# fpga33-serdes-power.net
KiCad netlist of a schematic drawn in Altium Designer
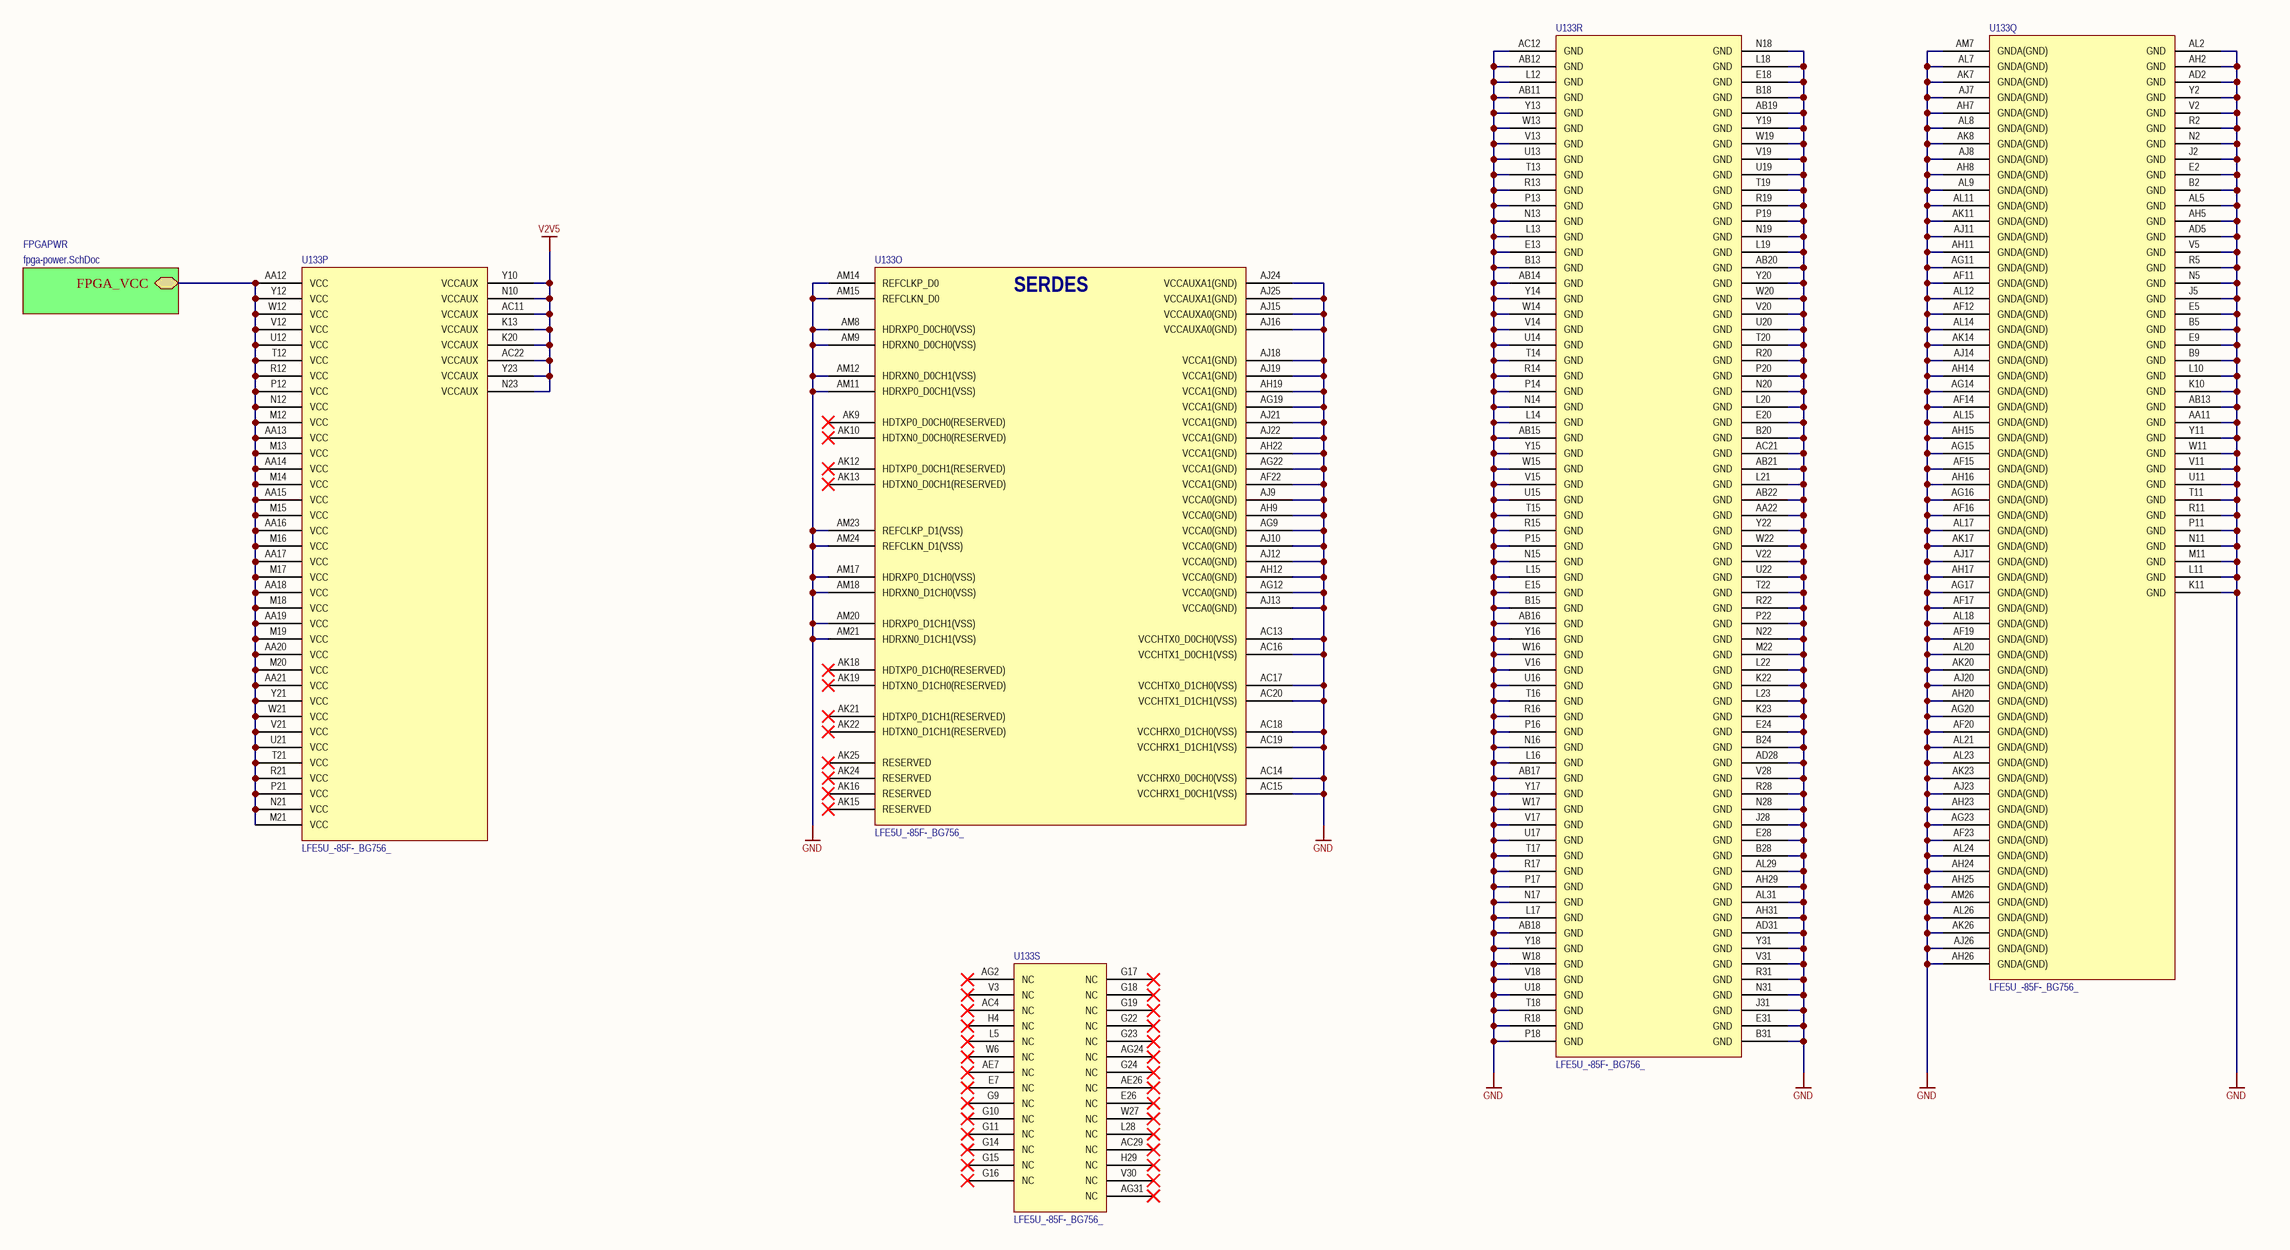
[diagram p0: fpga33-serdes-power.SchDoc]

(export (version "E")
  (design (tool "Eeschema 10.0.6"))
  (components
    (comp (ref "U133")
      (value "LFE5U_-85F-_BG756_")
      (footprint "lattice:caBGA756")
      (description "ECP5 FPGA, 85k LUT, 756-caBGA")
      (fields (field (name "MANUFACTURER") "Lattice Semiconductor"))
      (libsource (lib "lattice") (part "LFE5U_-85F-_BG756_"))
    )
  )
  (nets
    (net (code "1") (name "/FPGA_VCC") (class "Default")
      (node (ref "U133") (pin "AA12") (pinfunction "VCC_AA12") (pintype "power_in"))
      (node (ref "U133") (pin "AA13") (pinfunction "VCC_AA13") (pintype "power_in"))
      (node (ref "U133") (pin "AA14") (pinfunction "VCC_AA14") (pintype "power_in"))
      (node (ref "U133") (pin "AA15") (pinfunction "VCC_AA15") (pintype "power_in"))
      (node (ref "U133") (pin "AA16") (pinfunction "VCC_AA16") (pintype "power_in"))
      (node (ref "U133") (pin "AA17") (pinfunction "VCC_AA17") (pintype "power_in"))
      (node (ref "U133") (pin "AA18") (pinfunction "VCC_AA18") (pintype "power_in"))
      (node (ref "U133") (pin "AA19") (pinfunction "VCC_AA19") (pintype "power_in"))
      (node (ref "U133") (pin "AA20") (pinfunction "VCC_AA20") (pintype "power_in"))
      (node (ref "U133") (pin "AA21") (pinfunction "VCC_AA21") (pintype "power_in"))
      (node (ref "U133") (pin "M12") (pinfunction "VCC_M12") (pintype "power_in"))
      (node (ref "U133") (pin "M13") (pinfunction "VCC_M13") (pintype "power_in"))
      (node (ref "U133") (pin "M14") (pinfunction "VCC_M14") (pintype "power_in"))
      (node (ref "U133") (pin "M15") (pinfunction "VCC_M15") (pintype "power_in"))
      (node (ref "U133") (pin "M16") (pinfunction "VCC_M16") (pintype "power_in"))
      (node (ref "U133") (pin "M17") (pinfunction "VCC_M17") (pintype "power_in"))
      (node (ref "U133") (pin "M18") (pinfunction "VCC_M18") (pintype "power_in"))
      (node (ref "U133") (pin "M19") (pinfunction "VCC_M19") (pintype "power_in"))
      (node (ref "U133") (pin "M20") (pinfunction "VCC_M20") (pintype "power_in"))
      (node (ref "U133") (pin "M21") (pinfunction "VCC_M21") (pintype "power_in"))
      (node (ref "U133") (pin "N12") (pinfunction "VCC_N12") (pintype "power_in"))
      (node (ref "U133") (pin "N21") (pinfunction "VCC_N21") (pintype "power_in"))
      (node (ref "U133") (pin "P12") (pinfunction "VCC_P12") (pintype "power_in"))
      (node (ref "U133") (pin "P21") (pinfunction "VCC_P21") (pintype "power_in"))
      (node (ref "U133") (pin "R12") (pinfunction "VCC_R12") (pintype "power_in"))
      (node (ref "U133") (pin "R21") (pinfunction "VCC_R21") (pintype "power_in"))
      (node (ref "U133") (pin "T12") (pinfunction "VCC_T12") (pintype "power_in"))
      (node (ref "U133") (pin "T21") (pinfunction "VCC_T21") (pintype "power_in"))
      (node (ref "U133") (pin "U12") (pinfunction "VCC_U12") (pintype "power_in"))
      (node (ref "U133") (pin "U21") (pinfunction "VCC_U21") (pintype "power_in"))
      (node (ref "U133") (pin "V12") (pinfunction "VCC_V12") (pintype "power_in"))
      (node (ref "U133") (pin "V21") (pinfunction "VCC_V21") (pintype "power_in"))
      (node (ref "U133") (pin "W12") (pinfunction "VCC_W12") (pintype "power_in"))
      (node (ref "U133") (pin "W21") (pinfunction "VCC_W21") (pintype "power_in"))
      (node (ref "U133") (pin "Y12") (pinfunction "VCC_Y12") (pintype "power_in"))
      (node (ref "U133") (pin "Y21") (pinfunction "VCC_Y21") (pintype "power_in"))
    )
    (net (code "2") (name "GND") (class "Default")
      (node (ref "U133") (pin "AA11") (pinfunction "GND_AA11") (pintype "power_in"))
      (node (ref "U133") (pin "AA22") (pinfunction "GND_AA22") (pintype "power_in"))
      (node (ref "U133") (pin "AB11") (pinfunction "GND_AB11") (pintype "power_in"))
      (node (ref "U133") (pin "AB12") (pinfunction "GND_AB12") (pintype "power_in"))
      (node (ref "U133") (pin "AB13") (pinfunction "GND_AB13") (pintype "power_in"))
      (node (ref "U133") (pin "AB14") (pinfunction "GND_AB14") (pintype "power_in"))
      (node (ref "U133") (pin "AB15") (pinfunction "GND_AB15") (pintype "power_in"))
      (node (ref "U133") (pin "AB16") (pinfunction "GND_AB16") (pintype "power_in"))
      (node (ref "U133") (pin "AB17") (pinfunction "GND_AB17") (pintype "power_in"))
      (node (ref "U133") (pin "AB18") (pinfunction "GND_AB18") (pintype "power_in"))
      (node (ref "U133") (pin "AB19") (pinfunction "GND_AB19") (pintype "power_in"))
      (node (ref "U133") (pin "AB20") (pinfunction "GND_AB20") (pintype "power_in"))
      (node (ref "U133") (pin "AB21") (pinfunction "GND_AB21") (pintype "power_in"))
      (node (ref "U133") (pin "AB22") (pinfunction "GND_AB22") (pintype "power_in"))
      (node (ref "U133") (pin "AC12") (pinfunction "GND_AC12") (pintype "power_in"))
      (node (ref "U133") (pin "AC13") (pinfunction "VCCHTX0_D0CH0(VSS)_AC13") (pintype "power_in"))
      (node (ref "U133") (pin "AC14") (pinfunction "VCCHRX0_D0CH0(VSS)_AC14") (pintype "power_in"))
      (node (ref "U133") (pin "AC15") (pinfunction "VCCHRX1_D0CH1(VSS)_AC15") (pintype "power_in"))
      (node (ref "U133") (pin "AC16") (pinfunction "VCCHTX1_D0CH1(VSS)_AC16") (pintype "power_in"))
      (node (ref "U133") (pin "AC17") (pinfunction "VCCHTX0_D1CH0(VSS)_AC17") (pintype "power_in"))
      (node (ref "U133") (pin "AC18") (pinfunction "VCCHRX0_D1CH0(VSS)_AC18") (pintype "power_in"))
      (node (ref "U133") (pin "AC19") (pinfunction "VCCHRX1_D1CH1(VSS)_AC19") (pintype "power_in"))
      (node (ref "U133") (pin "AC20") (pinfunction "VCCHTX1_D1CH1(VSS)_AC20") (pintype "power_in"))
      (node (ref "U133") (pin "AC21") (pinfunction "GND_AC21") (pintype "power_in"))
      (node (ref "U133") (pin "AD2") (pinfunction "GND_AD2") (pintype "power_in"))
      (node (ref "U133") (pin "AD28") (pinfunction "GND_AD28") (pintype "power_in"))
      (node (ref "U133") (pin "AD31") (pinfunction "GND_AD31") (pintype "power_in"))
      (node (ref "U133") (pin "AD5") (pinfunction "GND_AD5") (pintype "power_in"))
      (node (ref "U133") (pin "AF11") (pinfunction "GNDA(GND)_AF11") (pintype "power_in"))
      (node (ref "U133") (pin "AF12") (pinfunction "GNDA(GND)_AF12") (pintype "power_in"))
      (node (ref "U133") (pin "AF14") (pinfunction "GNDA(GND)_AF14") (pintype "power_in"))
      (node (ref "U133") (pin "AF15") (pinfunction "GNDA(GND)_AF15") (pintype "power_in"))
      (node (ref "U133") (pin "AF16") (pinfunction "GNDA(GND)_AF16") (pintype "power_in"))
      (node (ref "U133") (pin "AF17") (pinfunction "GNDA(GND)_AF17") (pintype "power_in"))
      (node (ref "U133") (pin "AF19") (pinfunction "GNDA(GND)_AF19") (pintype "power_in"))
      (node (ref "U133") (pin "AF20") (pinfunction "GNDA(GND)_AF20") (pintype "power_in"))
      (node (ref "U133") (pin "AF22") (pinfunction "VCCA1(GND)_AF22") (pintype "power_in"))
      (node (ref "U133") (pin "AF23") (pinfunction "GNDA(GND)_AF23") (pintype "power_in"))
      (node (ref "U133") (pin "AG11") (pinfunction "GNDA(GND)_AG11") (pintype "power_in"))
      (node (ref "U133") (pin "AG12") (pinfunction "VCCA0(GND)_AG12") (pintype "power_in"))
      (node (ref "U133") (pin "AG14") (pinfunction "GNDA(GND)_AG14") (pintype "power_in"))
      (node (ref "U133") (pin "AG15") (pinfunction "GNDA(GND)_AG15") (pintype "power_in"))
      (node (ref "U133") (pin "AG16") (pinfunction "GNDA(GND)_AG16") (pintype "power_in"))
      (node (ref "U133") (pin "AG17") (pinfunction "GNDA(GND)_AG17") (pintype "power_in"))
      (node (ref "U133") (pin "AG19") (pinfunction "VCCA1(GND)_AG19") (pintype "power_in"))
      (node (ref "U133") (pin "AG20") (pinfunction "GNDA(GND)_AG20") (pintype "power_in"))
      (node (ref "U133") (pin "AG22") (pinfunction "VCCA1(GND)_AG22") (pintype "power_in"))
      (node (ref "U133") (pin "AG23") (pinfunction "GNDA(GND)_AG23") (pintype "power_in"))
      (node (ref "U133") (pin "AG9") (pinfunction "VCCA0(GND)_AG9") (pintype "power_in"))
      (node (ref "U133") (pin "AH11") (pinfunction "GNDA(GND)_AH11") (pintype "power_in"))
      (node (ref "U133") (pin "AH12") (pinfunction "VCCA0(GND)_AH12") (pintype "power_in"))
      (node (ref "U133") (pin "AH14") (pinfunction "GNDA(GND)_AH14") (pintype "power_in"))
      (node (ref "U133") (pin "AH15") (pinfunction "GNDA(GND)_AH15") (pintype "power_in"))
      (node (ref "U133") (pin "AH16") (pinfunction "GNDA(GND)_AH16") (pintype "power_in"))
      (node (ref "U133") (pin "AH17") (pinfunction "GNDA(GND)_AH17") (pintype "power_in"))
      (node (ref "U133") (pin "AH19") (pinfunction "VCCA1(GND)_AH19") (pintype "power_in"))
      (node (ref "U133") (pin "AH2") (pinfunction "GND_AH2") (pintype "power_in"))
      (node (ref "U133") (pin "AH20") (pinfunction "GNDA(GND)_AH20") (pintype "power_in"))
      (node (ref "U133") (pin "AH22") (pinfunction "VCCA1(GND)_AH22") (pintype "power_in"))
      (node (ref "U133") (pin "AH23") (pinfunction "GNDA(GND)_AH23") (pintype "power_in"))
      (node (ref "U133") (pin "AH24") (pinfunction "GNDA(GND)_AH24") (pintype "power_in"))
      (node (ref "U133") (pin "AH25") (pinfunction "GNDA(GND)_AH25") (pintype "power_in"))
      (node (ref "U133") (pin "AH26") (pinfunction "GNDA(GND)_AH26") (pintype "power_in"))
      (node (ref "U133") (pin "AH29") (pinfunction "GND_AH29") (pintype "power_in"))
      (node (ref "U133") (pin "AH31") (pinfunction "GND_AH31") (pintype "power_in"))
      (node (ref "U133") (pin "AH5") (pinfunction "GND_AH5") (pintype "power_in"))
      (node (ref "U133") (pin "AH7") (pinfunction "GNDA(GND)_AH7") (pintype "power_in"))
      (node (ref "U133") (pin "AH8") (pinfunction "GNDA(GND)_AH8") (pintype "power_in"))
      (node (ref "U133") (pin "AH9") (pinfunction "VCCA0(GND)_AH9") (pintype "power_in"))
      (node (ref "U133") (pin "AJ10") (pinfunction "VCCA0(GND)_AJ10") (pintype "power_in"))
      (node (ref "U133") (pin "AJ11") (pinfunction "GNDA(GND)_AJ11") (pintype "power_in"))
      (node (ref "U133") (pin "AJ12") (pinfunction "VCCA0(GND)_AJ12") (pintype "power_in"))
      (node (ref "U133") (pin "AJ13") (pinfunction "VCCA0(GND)_AJ13") (pintype "power_in"))
      (node (ref "U133") (pin "AJ14") (pinfunction "GNDA(GND)_AJ14") (pintype "power_in"))
      (node (ref "U133") (pin "AJ15") (pinfunction "VCCAUXA0(GND)_AJ15") (pintype "power_in"))
      (node (ref "U133") (pin "AJ16") (pinfunction "VCCAUXA0(GND)_AJ16") (pintype "power_in"))
      (node (ref "U133") (pin "AJ17") (pinfunction "GNDA(GND)_AJ17") (pintype "power_in"))
      (node (ref "U133") (pin "AJ18") (pinfunction "VCCA1(GND)_AJ18") (pintype "power_in"))
      (node (ref "U133") (pin "AJ19") (pinfunction "VCCA1(GND)_AJ19") (pintype "power_in"))
      (node (ref "U133") (pin "AJ20") (pinfunction "GNDA(GND)_AJ20") (pintype "power_in"))
      (node (ref "U133") (pin "AJ21") (pinfunction "VCCA1(GND)_AJ21") (pintype "power_in"))
      (node (ref "U133") (pin "AJ22") (pinfunction "VCCA1(GND)_AJ22") (pintype "power_in"))
      (node (ref "U133") (pin "AJ23") (pinfunction "GNDA(GND)_AJ23") (pintype "power_in"))
      (node (ref "U133") (pin "AJ24") (pinfunction "VCCAUXA1(GND)_AJ24") (pintype "power_in"))
      (node (ref "U133") (pin "AJ25") (pinfunction "VCCAUXA1(GND)_AJ25") (pintype "power_in"))
      (node (ref "U133") (pin "AJ26") (pinfunction "GNDA(GND)_AJ26") (pintype "power_in"))
      (node (ref "U133") (pin "AJ7") (pinfunction "GNDA(GND)_AJ7") (pintype "power_in"))
      (node (ref "U133") (pin "AJ8") (pinfunction "GNDA(GND)_AJ8") (pintype "power_in"))
      (node (ref "U133") (pin "AJ9") (pinfunction "VCCA0(GND)_AJ9") (pintype "power_in"))
      (node (ref "U133") (pin "AK11") (pinfunction "GNDA(GND)_AK11") (pintype "power_in"))
      (node (ref "U133") (pin "AK14") (pinfunction "GNDA(GND)_AK14") (pintype "power_in"))
      (node (ref "U133") (pin "AK17") (pinfunction "GNDA(GND)_AK17") (pintype "power_in"))
      (node (ref "U133") (pin "AK20") (pinfunction "GNDA(GND)_AK20") (pintype "power_in"))
      (node (ref "U133") (pin "AK23") (pinfunction "GNDA(GND)_AK23") (pintype "power_in"))
      (node (ref "U133") (pin "AK26") (pinfunction "GNDA(GND)_AK26") (pintype "power_in"))
      (node (ref "U133") (pin "AK7") (pinfunction "GNDA(GND)_AK7") (pintype "power_in"))
      (node (ref "U133") (pin "AK8") (pinfunction "GNDA(GND)_AK8") (pintype "power_in"))
      (node (ref "U133") (pin "AL11") (pinfunction "GNDA(GND)_AL11") (pintype "power_in"))
      (node (ref "U133") (pin "AL12") (pinfunction "GNDA(GND)_AL12") (pintype "power_in"))
      (node (ref "U133") (pin "AL14") (pinfunction "GNDA(GND)_AL14") (pintype "power_in"))
      (node (ref "U133") (pin "AL15") (pinfunction "GNDA(GND)_AL15") (pintype "power_in"))
      (node (ref "U133") (pin "AL17") (pinfunction "GNDA(GND)_AL17") (pintype "power_in"))
      (node (ref "U133") (pin "AL18") (pinfunction "GNDA(GND)_AL18") (pintype "power_in"))
      (node (ref "U133") (pin "AL2") (pinfunction "GND_AL2") (pintype "power_in"))
      (node (ref "U133") (pin "AL20") (pinfunction "GNDA(GND)_AL20") (pintype "power_in"))
      (node (ref "U133") (pin "AL21") (pinfunction "GNDA(GND)_AL21") (pintype "power_in"))
      (node (ref "U133") (pin "AL23") (pinfunction "GNDA(GND)_AL23") (pintype "power_in"))
      (node (ref "U133") (pin "AL24") (pinfunction "GNDA(GND)_AL24") (pintype "power_in"))
      (node (ref "U133") (pin "AL26") (pinfunction "GNDA(GND)_AL26") (pintype "power_in"))
      (node (ref "U133") (pin "AL29") (pinfunction "GND_AL29") (pintype "power_in"))
      (node (ref "U133") (pin "AL31") (pinfunction "GND_AL31") (pintype "power_in"))
      (node (ref "U133") (pin "AL5") (pinfunction "GND_AL5") (pintype "power_in"))
      (node (ref "U133") (pin "AL7") (pinfunction "GNDA(GND)_AL7") (pintype "power_in"))
      (node (ref "U133") (pin "AL8") (pinfunction "GNDA(GND)_AL8") (pintype "power_in"))
      (node (ref "U133") (pin "AL9") (pinfunction "GNDA(GND)_AL9") (pintype "power_in"))
      (node (ref "U133") (pin "AM11") (pinfunction "HDRXP0_D0CH1(VSS)_AM11") (pintype "passive"))
      (node (ref "U133") (pin "AM12") (pinfunction "HDRXN0_D0CH1(VSS)_AM12") (pintype "passive"))
      (node (ref "U133") (pin "AM14") (pinfunction "REFCLKP_D0_AM14") (pintype "passive"))
      (node (ref "U133") (pin "AM15") (pinfunction "REFCLKN_D0_AM15") (pintype "passive"))
      (node (ref "U133") (pin "AM17") (pinfunction "HDRXP0_D1CH0(VSS)_AM17") (pintype "passive"))
      (node (ref "U133") (pin "AM18") (pinfunction "HDRXN0_D1CH0(VSS)_AM18") (pintype "passive"))
      (node (ref "U133") (pin "AM20") (pinfunction "HDRXP0_D1CH1(VSS)_AM20") (pintype "passive"))
      (node (ref "U133") (pin "AM21") (pinfunction "HDRXN0_D1CH1(VSS)_AM21") (pintype "passive"))
      (node (ref "U133") (pin "AM23") (pinfunction "REFCLKP_D1(VSS)_AM23") (pintype "passive"))
      (node (ref "U133") (pin "AM24") (pinfunction "REFCLKN_D1(VSS)_AM24") (pintype "passive"))
      (node (ref "U133") (pin "AM26") (pinfunction "GNDA(GND)_AM26") (pintype "power_in"))
      (node (ref "U133") (pin "AM7") (pinfunction "GNDA(GND)_AM7") (pintype "power_in"))
      (node (ref "U133") (pin "AM8") (pinfunction "HDRXP0_D0CH0(VSS)_AM8") (pintype "passive"))
      (node (ref "U133") (pin "AM9") (pinfunction "HDRXN0_D0CH0(VSS)_AM9") (pintype "passive"))
      (node (ref "U133") (pin "B13") (pinfunction "GND_B13") (pintype "power_in"))
      (node (ref "U133") (pin "B15") (pinfunction "GND_B15") (pintype "power_in"))
      (node (ref "U133") (pin "B18") (pinfunction "GND_B18") (pintype "power_in"))
      (node (ref "U133") (pin "B2") (pinfunction "GND_B2") (pintype "power_in"))
      (node (ref "U133") (pin "B20") (pinfunction "GND_B20") (pintype "power_in"))
      (node (ref "U133") (pin "B24") (pinfunction "GND_B24") (pintype "power_in"))
      (node (ref "U133") (pin "B28") (pinfunction "GND_B28") (pintype "power_in"))
      (node (ref "U133") (pin "B31") (pinfunction "GND_B31") (pintype "power_in"))
      (node (ref "U133") (pin "B5") (pinfunction "GND_B5") (pintype "power_in"))
      (node (ref "U133") (pin "B9") (pinfunction "GND_B9") (pintype "power_in"))
      (node (ref "U133") (pin "E13") (pinfunction "GND_E13") (pintype "power_in"))
      (node (ref "U133") (pin "E15") (pinfunction "GND_E15") (pintype "power_in"))
      (node (ref "U133") (pin "E18") (pinfunction "GND_E18") (pintype "power_in"))
      (node (ref "U133") (pin "E2") (pinfunction "GND_E2") (pintype "power_in"))
      (node (ref "U133") (pin "E20") (pinfunction "GND_E20") (pintype "power_in"))
      (node (ref "U133") (pin "E24") (pinfunction "GND_E24") (pintype "power_in"))
      (node (ref "U133") (pin "E28") (pinfunction "GND_E28") (pintype "power_in"))
      (node (ref "U133") (pin "E31") (pinfunction "GND_E31") (pintype "power_in"))
      (node (ref "U133") (pin "E5") (pinfunction "GND_E5") (pintype "power_in"))
      (node (ref "U133") (pin "E9") (pinfunction "GND_E9") (pintype "power_in"))
      (node (ref "U133") (pin "J2") (pinfunction "GND_J2") (pintype "power_in"))
      (node (ref "U133") (pin "J28") (pinfunction "GND_J28") (pintype "power_in"))
      (node (ref "U133") (pin "J31") (pinfunction "GND_J31") (pintype "power_in"))
      (node (ref "U133") (pin "J5") (pinfunction "GND_J5") (pintype "power_in"))
      (node (ref "U133") (pin "K10") (pinfunction "GND_K10") (pintype "power_in"))
      (node (ref "U133") (pin "K11") (pinfunction "GND_K11") (pintype "power_in"))
      (node (ref "U133") (pin "K22") (pinfunction "GND_K22") (pintype "power_in"))
      (node (ref "U133") (pin "K23") (pinfunction "GND_K23") (pintype "power_in"))
      (node (ref "U133") (pin "L10") (pinfunction "GND_L10") (pintype "power_in"))
      (node (ref "U133") (pin "L11") (pinfunction "GND_L11") (pintype "power_in"))
      (node (ref "U133") (pin "L12") (pinfunction "GND_L12") (pintype "power_in"))
      (node (ref "U133") (pin "L13") (pinfunction "GND_L13") (pintype "power_in"))
      (node (ref "U133") (pin "L14") (pinfunction "GND_L14") (pintype "power_in"))
      (node (ref "U133") (pin "L15") (pinfunction "GND_L15") (pintype "power_in"))
      (node (ref "U133") (pin "L16") (pinfunction "GND_L16") (pintype "power_in"))
      (node (ref "U133") (pin "L17") (pinfunction "GND_L17") (pintype "power_in"))
      (node (ref "U133") (pin "L18") (pinfunction "GND_L18") (pintype "power_in"))
      (node (ref "U133") (pin "L19") (pinfunction "GND_L19") (pintype "power_in"))
      (node (ref "U133") (pin "L20") (pinfunction "GND_L20") (pintype "power_in"))
      (node (ref "U133") (pin "L21") (pinfunction "GND_L21") (pintype "power_in"))
      (node (ref "U133") (pin "L22") (pinfunction "GND_L22") (pintype "power_in"))
      (node (ref "U133") (pin "L23") (pinfunction "GND_L23") (pintype "power_in"))
      (node (ref "U133") (pin "M11") (pinfunction "GND_M11") (pintype "power_in"))
      (node (ref "U133") (pin "M22") (pinfunction "GND_M22") (pintype "power_in"))
      (node (ref "U133") (pin "N11") (pinfunction "GND_N11") (pintype "power_in"))
      (node (ref "U133") (pin "N13") (pinfunction "GND_N13") (pintype "power_in"))
      (node (ref "U133") (pin "N14") (pinfunction "GND_N14") (pintype "power_in"))
      (node (ref "U133") (pin "N15") (pinfunction "GND_N15") (pintype "power_in"))
      (node (ref "U133") (pin "N16") (pinfunction "GND_N16") (pintype "power_in"))
      (node (ref "U133") (pin "N17") (pinfunction "GND_N17") (pintype "power_in"))
      (node (ref "U133") (pin "N18") (pinfunction "GND_N18") (pintype "power_in"))
      (node (ref "U133") (pin "N19") (pinfunction "GND_N19") (pintype "power_in"))
      (node (ref "U133") (pin "N2") (pinfunction "GND_N2") (pintype "power_in"))
      (node (ref "U133") (pin "N20") (pinfunction "GND_N20") (pintype "power_in"))
      (node (ref "U133") (pin "N22") (pinfunction "GND_N22") (pintype "power_in"))
      (node (ref "U133") (pin "N28") (pinfunction "GND_N28") (pintype "power_in"))
      (node (ref "U133") (pin "N31") (pinfunction "GND_N31") (pintype "power_in"))
      (node (ref "U133") (pin "N5") (pinfunction "GND_N5") (pintype "power_in"))
      (node (ref "U133") (pin "P11") (pinfunction "GND_P11") (pintype "power_in"))
      (node (ref "U133") (pin "P13") (pinfunction "GND_P13") (pintype "power_in"))
      (node (ref "U133") (pin "P14") (pinfunction "GND_P14") (pintype "power_in"))
      (node (ref "U133") (pin "P15") (pinfunction "GND_P15") (pintype "power_in"))
      (node (ref "U133") (pin "P16") (pinfunction "GND_P16") (pintype "power_in"))
      (node (ref "U133") (pin "P17") (pinfunction "GND_P17") (pintype "power_in"))
      (node (ref "U133") (pin "P18") (pinfunction "GND_P18") (pintype "power_in"))
      (node (ref "U133") (pin "P19") (pinfunction "GND_P19") (pintype "power_in"))
      (node (ref "U133") (pin "P20") (pinfunction "GND_P20") (pintype "power_in"))
      (node (ref "U133") (pin "P22") (pinfunction "GND_P22") (pintype "power_in"))
      (node (ref "U133") (pin "R11") (pinfunction "GND_R11") (pintype "power_in"))
      (node (ref "U133") (pin "R13") (pinfunction "GND_R13") (pintype "power_in"))
      (node (ref "U133") (pin "R14") (pinfunction "GND_R14") (pintype "power_in"))
      (node (ref "U133") (pin "R15") (pinfunction "GND_R15") (pintype "power_in"))
      (node (ref "U133") (pin "R16") (pinfunction "GND_R16") (pintype "power_in"))
      (node (ref "U133") (pin "R17") (pinfunction "GND_R17") (pintype "power_in"))
      (node (ref "U133") (pin "R18") (pinfunction "GND_R18") (pintype "power_in"))
      (node (ref "U133") (pin "R19") (pinfunction "GND_R19") (pintype "power_in"))
      (node (ref "U133") (pin "R2") (pinfunction "GND_R2") (pintype "power_in"))
      (node (ref "U133") (pin "R20") (pinfunction "GND_R20") (pintype "power_in"))
      (node (ref "U133") (pin "R22") (pinfunction "GND_R22") (pintype "power_in"))
      (node (ref "U133") (pin "R28") (pinfunction "GND_R28") (pintype "power_in"))
      (node (ref "U133") (pin "R31") (pinfunction "GND_R31") (pintype "power_in"))
      (node (ref "U133") (pin "R5") (pinfunction "GND_R5") (pintype "power_in"))
      (node (ref "U133") (pin "T11") (pinfunction "GND_T11") (pintype "power_in"))
      (node (ref "U133") (pin "T13") (pinfunction "GND_T13") (pintype "power_in"))
      (node (ref "U133") (pin "T14") (pinfunction "GND_T14") (pintype "power_in"))
      (node (ref "U133") (pin "T15") (pinfunction "GND_T15") (pintype "power_in"))
      (node (ref "U133") (pin "T16") (pinfunction "GND_T16") (pintype "power_in"))
      (node (ref "U133") (pin "T17") (pinfunction "GND_T17") (pintype "power_in"))
      (node (ref "U133") (pin "T18") (pinfunction "GND_T18") (pintype "power_in"))
      (node (ref "U133") (pin "T19") (pinfunction "GND_T19") (pintype "power_in"))
      (node (ref "U133") (pin "T20") (pinfunction "GND_T20") (pintype "power_in"))
      (node (ref "U133") (pin "T22") (pinfunction "GND_T22") (pintype "power_in"))
      (node (ref "U133") (pin "U11") (pinfunction "GND_U11") (pintype "power_in"))
      (node (ref "U133") (pin "U13") (pinfunction "GND_U13") (pintype "power_in"))
      (node (ref "U133") (pin "U14") (pinfunction "GND_U14") (pintype "power_in"))
      (node (ref "U133") (pin "U15") (pinfunction "GND_U15") (pintype "power_in"))
      (node (ref "U133") (pin "U16") (pinfunction "GND_U16") (pintype "power_in"))
      (node (ref "U133") (pin "U17") (pinfunction "GND_U17") (pintype "power_in"))
      (node (ref "U133") (pin "U18") (pinfunction "GND_U18") (pintype "power_in"))
      (node (ref "U133") (pin "U19") (pinfunction "GND_U19") (pintype "power_in"))
      (node (ref "U133") (pin "U20") (pinfunction "GND_U20") (pintype "power_in"))
      (node (ref "U133") (pin "U22") (pinfunction "GND_U22") (pintype "power_in"))
      (node (ref "U133") (pin "V11") (pinfunction "GND_V11") (pintype "power_in"))
      (node (ref "U133") (pin "V13") (pinfunction "GND_V13") (pintype "power_in"))
      (node (ref "U133") (pin "V14") (pinfunction "GND_V14") (pintype "power_in"))
      (node (ref "U133") (pin "V15") (pinfunction "GND_V15") (pintype "power_in"))
      (node (ref "U133") (pin "V16") (pinfunction "GND_V16") (pintype "power_in"))
      (node (ref "U133") (pin "V17") (pinfunction "GND_V17") (pintype "power_in"))
      (node (ref "U133") (pin "V18") (pinfunction "GND_V18") (pintype "power_in"))
      (node (ref "U133") (pin "V19") (pinfunction "GND_V19") (pintype "power_in"))
      (node (ref "U133") (pin "V2") (pinfunction "GND_V2") (pintype "power_in"))
      (node (ref "U133") (pin "V20") (pinfunction "GND_V20") (pintype "power_in"))
      (node (ref "U133") (pin "V22") (pinfunction "GND_V22") (pintype "power_in"))
      (node (ref "U133") (pin "V28") (pinfunction "GND_V28") (pintype "power_in"))
      (node (ref "U133") (pin "V31") (pinfunction "GND_V31") (pintype "power_in"))
      (node (ref "U133") (pin "V5") (pinfunction "GND_V5") (pintype "power_in"))
      (node (ref "U133") (pin "W11") (pinfunction "GND_W11") (pintype "power_in"))
      (node (ref "U133") (pin "W13") (pinfunction "GND_W13") (pintype "power_in"))
      (node (ref "U133") (pin "W14") (pinfunction "GND_W14") (pintype "power_in"))
      (node (ref "U133") (pin "W15") (pinfunction "GND_W15") (pintype "power_in"))
      (node (ref "U133") (pin "W16") (pinfunction "GND_W16") (pintype "power_in"))
      (node (ref "U133") (pin "W17") (pinfunction "GND_W17") (pintype "power_in"))
      (node (ref "U133") (pin "W18") (pinfunction "GND_W18") (pintype "power_in"))
      (node (ref "U133") (pin "W19") (pinfunction "GND_W19") (pintype "power_in"))
      (node (ref "U133") (pin "W20") (pinfunction "GND_W20") (pintype "power_in"))
      (node (ref "U133") (pin "W22") (pinfunction "GND_W22") (pintype "power_in"))
      (node (ref "U133") (pin "Y11") (pinfunction "GND_Y11") (pintype "power_in"))
      (node (ref "U133") (pin "Y13") (pinfunction "GND_Y13") (pintype "power_in"))
      (node (ref "U133") (pin "Y14") (pinfunction "GND_Y14") (pintype "power_in"))
      (node (ref "U133") (pin "Y15") (pinfunction "GND_Y15") (pintype "power_in"))
      (node (ref "U133") (pin "Y16") (pinfunction "GND_Y16") (pintype "power_in"))
      (node (ref "U133") (pin "Y17") (pinfunction "GND_Y17") (pintype "power_in"))
      (node (ref "U133") (pin "Y18") (pinfunction "GND_Y18") (pintype "power_in"))
      (node (ref "U133") (pin "Y19") (pinfunction "GND_Y19") (pintype "power_in"))
      (node (ref "U133") (pin "Y2") (pinfunction "GND_Y2") (pintype "power_in"))
      (node (ref "U133") (pin "Y20") (pinfunction "GND_Y20") (pintype "power_in"))
      (node (ref "U133") (pin "Y22") (pinfunction "GND_Y22") (pintype "power_in"))
      (node (ref "U133") (pin "Y31") (pinfunction "GND_Y31") (pintype "power_in"))
    )
    (net (code "3") (name "V2V5") (class "Default")
      (node (ref "U133") (pin "AC11") (pinfunction "VCCAUX_AC11") (pintype "power_in"))
      (node (ref "U133") (pin "AC22") (pinfunction "VCCAUX_AC22") (pintype "power_in"))
      (node (ref "U133") (pin "K13") (pinfunction "VCCAUX_K13") (pintype "power_in"))
      (node (ref "U133") (pin "K20") (pinfunction "VCCAUX_K20") (pintype "power_in"))
      (node (ref "U133") (pin "N10") (pinfunction "VCCAUX_N10") (pintype "power_in"))
      (node (ref "U133") (pin "N23") (pinfunction "VCCAUX_N23") (pintype "power_in"))
      (node (ref "U133") (pin "Y10") (pinfunction "VCCAUX_Y10") (pintype "power_in"))
      (node (ref "U133") (pin "Y23") (pinfunction "VCCAUX_Y23") (pintype "power_in"))
    )
    (net (code "4") (name "unconnected-(U133O-HDTXN0_D0CH0(RESERVED)-PadAK10)") (class "Default")
      (node (ref "U133") (pin "AK10") (pinfunction "HDTXN0_D0CH0(RESERVED)_AK10") (pintype "passive+no_connect"))
    )
    (net (code "5") (name "unconnected-(U133O-HDTXN0_D0CH1(RESERVED)-PadAK13)") (class "Default")
      (node (ref "U133") (pin "AK13") (pinfunction "HDTXN0_D0CH1(RESERVED)_AK13") (pintype "passive+no_connect"))
    )
    (net (code "6") (name "unconnected-(U133O-HDTXN0_D1CH0(RESERVED)-PadAK19)") (class "Default")
      (node (ref "U133") (pin "AK19") (pinfunction "HDTXN0_D1CH0(RESERVED)_AK19") (pintype "passive+no_connect"))
    )
    (net (code "7") (name "unconnected-(U133O-HDTXN0_D1CH1(RESERVED)-PadAK22)") (class "Default")
      (node (ref "U133") (pin "AK22") (pinfunction "HDTXN0_D1CH1(RESERVED)_AK22") (pintype "passive+no_connect"))
    )
    (net (code "8") (name "unconnected-(U133O-HDTXP0_D0CH0(RESERVED)-PadAK9)") (class "Default")
      (node (ref "U133") (pin "AK9") (pinfunction "HDTXP0_D0CH0(RESERVED)_AK9") (pintype "passive+no_connect"))
    )
    (net (code "9") (name "unconnected-(U133O-HDTXP0_D0CH1(RESERVED)-PadAK12)") (class "Default")
      (node (ref "U133") (pin "AK12") (pinfunction "HDTXP0_D0CH1(RESERVED)_AK12") (pintype "passive+no_connect"))
    )
    (net (code "10") (name "unconnected-(U133O-HDTXP0_D1CH0(RESERVED)-PadAK18)") (class "Default")
      (node (ref "U133") (pin "AK18") (pinfunction "HDTXP0_D1CH0(RESERVED)_AK18") (pintype "passive+no_connect"))
    )
    (net (code "11") (name "unconnected-(U133O-HDTXP0_D1CH1(RESERVED)-PadAK21)") (class "Default")
      (node (ref "U133") (pin "AK21") (pinfunction "HDTXP0_D1CH1(RESERVED)_AK21") (pintype "passive+no_connect"))
    )
    (net (code "12") (name "unconnected-(U133O-RESERVED-PadAK15)") (class "Default")
      (node (ref "U133") (pin "AK15") (pinfunction "RESERVED_AK15") (pintype "passive+no_connect"))
    )
    (net (code "13") (name "unconnected-(U133O-RESERVED-PadAK16)") (class "Default")
      (node (ref "U133") (pin "AK16") (pinfunction "RESERVED_AK16") (pintype "passive+no_connect"))
    )
    (net (code "14") (name "unconnected-(U133O-RESERVED-PadAK24)") (class "Default")
      (node (ref "U133") (pin "AK24") (pinfunction "RESERVED_AK24") (pintype "passive+no_connect"))
    )
    (net (code "15") (name "unconnected-(U133O-RESERVED-PadAK25)") (class "Default")
      (node (ref "U133") (pin "AK25") (pinfunction "RESERVED_AK25") (pintype "passive+no_connect"))
    )
    (net (code "16") (name "unconnected-(U133S-NC-PadAC4)") (class "Default")
      (node (ref "U133") (pin "AC4") (pinfunction "NC_AC4") (pintype "passive+no_connect"))
    )
    (net (code "17") (name "unconnected-(U133S-NC-PadAC29)") (class "Default")
      (node (ref "U133") (pin "AC29") (pinfunction "NC_AC29") (pintype "passive+no_connect"))
    )
    (net (code "18") (name "unconnected-(U133S-NC-PadAE7)") (class "Default")
      (node (ref "U133") (pin "AE7") (pinfunction "NC_AE7") (pintype "passive+no_connect"))
    )
    (net (code "19") (name "unconnected-(U133S-NC-PadAE26)") (class "Default")
      (node (ref "U133") (pin "AE26") (pinfunction "NC_AE26") (pintype "passive+no_connect"))
    )
    (net (code "20") (name "unconnected-(U133S-NC-PadAG2)") (class "Default")
      (node (ref "U133") (pin "AG2") (pinfunction "NC_AG2") (pintype "passive+no_connect"))
    )
    (net (code "21") (name "unconnected-(U133S-NC-PadAG24)") (class "Default")
      (node (ref "U133") (pin "AG24") (pinfunction "NC_AG24") (pintype "passive+no_connect"))
    )
    (net (code "22") (name "unconnected-(U133S-NC-PadAG31)") (class "Default")
      (node (ref "U133") (pin "AG31") (pinfunction "NC_AG31") (pintype "passive+no_connect"))
    )
    (net (code "23") (name "unconnected-(U133S-NC-PadE7)") (class "Default")
      (node (ref "U133") (pin "E7") (pinfunction "NC_E7") (pintype "passive+no_connect"))
    )
    (net (code "24") (name "unconnected-(U133S-NC-PadE26)") (class "Default")
      (node (ref "U133") (pin "E26") (pinfunction "NC_E26") (pintype "passive+no_connect"))
    )
    (net (code "25") (name "unconnected-(U133S-NC-PadG9)") (class "Default")
      (node (ref "U133") (pin "G9") (pinfunction "NC_G9") (pintype "passive+no_connect"))
    )
    (net (code "26") (name "unconnected-(U133S-NC-PadG10)") (class "Default")
      (node (ref "U133") (pin "G10") (pinfunction "NC_G10") (pintype "passive+no_connect"))
    )
    (net (code "27") (name "unconnected-(U133S-NC-PadG11)") (class "Default")
      (node (ref "U133") (pin "G11") (pinfunction "NC_G11") (pintype "passive+no_connect"))
    )
    (net (code "28") (name "unconnected-(U133S-NC-PadG14)") (class "Default")
      (node (ref "U133") (pin "G14") (pinfunction "NC_G14") (pintype "passive+no_connect"))
    )
    (net (code "29") (name "unconnected-(U133S-NC-PadG15)") (class "Default")
      (node (ref "U133") (pin "G15") (pinfunction "NC_G15") (pintype "passive+no_connect"))
    )
    (net (code "30") (name "unconnected-(U133S-NC-PadG16)") (class "Default")
      (node (ref "U133") (pin "G16") (pinfunction "NC_G16") (pintype "passive+no_connect"))
    )
    (net (code "31") (name "unconnected-(U133S-NC-PadG17)") (class "Default")
      (node (ref "U133") (pin "G17") (pinfunction "NC_G17") (pintype "passive+no_connect"))
    )
    (net (code "32") (name "unconnected-(U133S-NC-PadG18)") (class "Default")
      (node (ref "U133") (pin "G18") (pinfunction "NC_G18") (pintype "passive+no_connect"))
    )
    (net (code "33") (name "unconnected-(U133S-NC-PadG19)") (class "Default")
      (node (ref "U133") (pin "G19") (pinfunction "NC_G19") (pintype "passive+no_connect"))
    )
    (net (code "34") (name "unconnected-(U133S-NC-PadG22)") (class "Default")
      (node (ref "U133") (pin "G22") (pinfunction "NC_G22") (pintype "passive+no_connect"))
    )
    (net (code "35") (name "unconnected-(U133S-NC-PadG23)") (class "Default")
      (node (ref "U133") (pin "G23") (pinfunction "NC_G23") (pintype "passive+no_connect"))
    )
    (net (code "36") (name "unconnected-(U133S-NC-PadG24)") (class "Default")
      (node (ref "U133") (pin "G24") (pinfunction "NC_G24") (pintype "passive+no_connect"))
    )
    (net (code "37") (name "unconnected-(U133S-NC-PadH4)") (class "Default")
      (node (ref "U133") (pin "H4") (pinfunction "NC_H4") (pintype "passive+no_connect"))
    )
    (net (code "38") (name "unconnected-(U133S-NC-PadH29)") (class "Default")
      (node (ref "U133") (pin "H29") (pinfunction "NC_H29") (pintype "passive+no_connect"))
    )
    (net (code "39") (name "unconnected-(U133S-NC-PadL5)") (class "Default")
      (node (ref "U133") (pin "L5") (pinfunction "NC_L5") (pintype "passive+no_connect"))
    )
    (net (code "40") (name "unconnected-(U133S-NC-PadL28)") (class "Default")
      (node (ref "U133") (pin "L28") (pinfunction "NC_L28") (pintype "passive+no_connect"))
    )
    (net (code "41") (name "unconnected-(U133S-NC-PadV3)") (class "Default")
      (node (ref "U133") (pin "V3") (pinfunction "NC_V3") (pintype "passive+no_connect"))
    )
    (net (code "42") (name "unconnected-(U133S-NC-PadV30)") (class "Default")
      (node (ref "U133") (pin "V30") (pinfunction "NC_V30") (pintype "passive+no_connect"))
    )
    (net (code "43") (name "unconnected-(U133S-NC-PadW6)") (class "Default")
      (node (ref "U133") (pin "W6") (pinfunction "NC_W6") (pintype "passive+no_connect"))
    )
    (net (code "44") (name "unconnected-(U133S-NC-PadW27)") (class "Default")
      (node (ref "U133") (pin "W27") (pinfunction "NC_W27") (pintype "passive+no_connect"))
    )
  )
)
